# High_Freq.net
KiCad netlist of a schematic drawn in Altium Designer
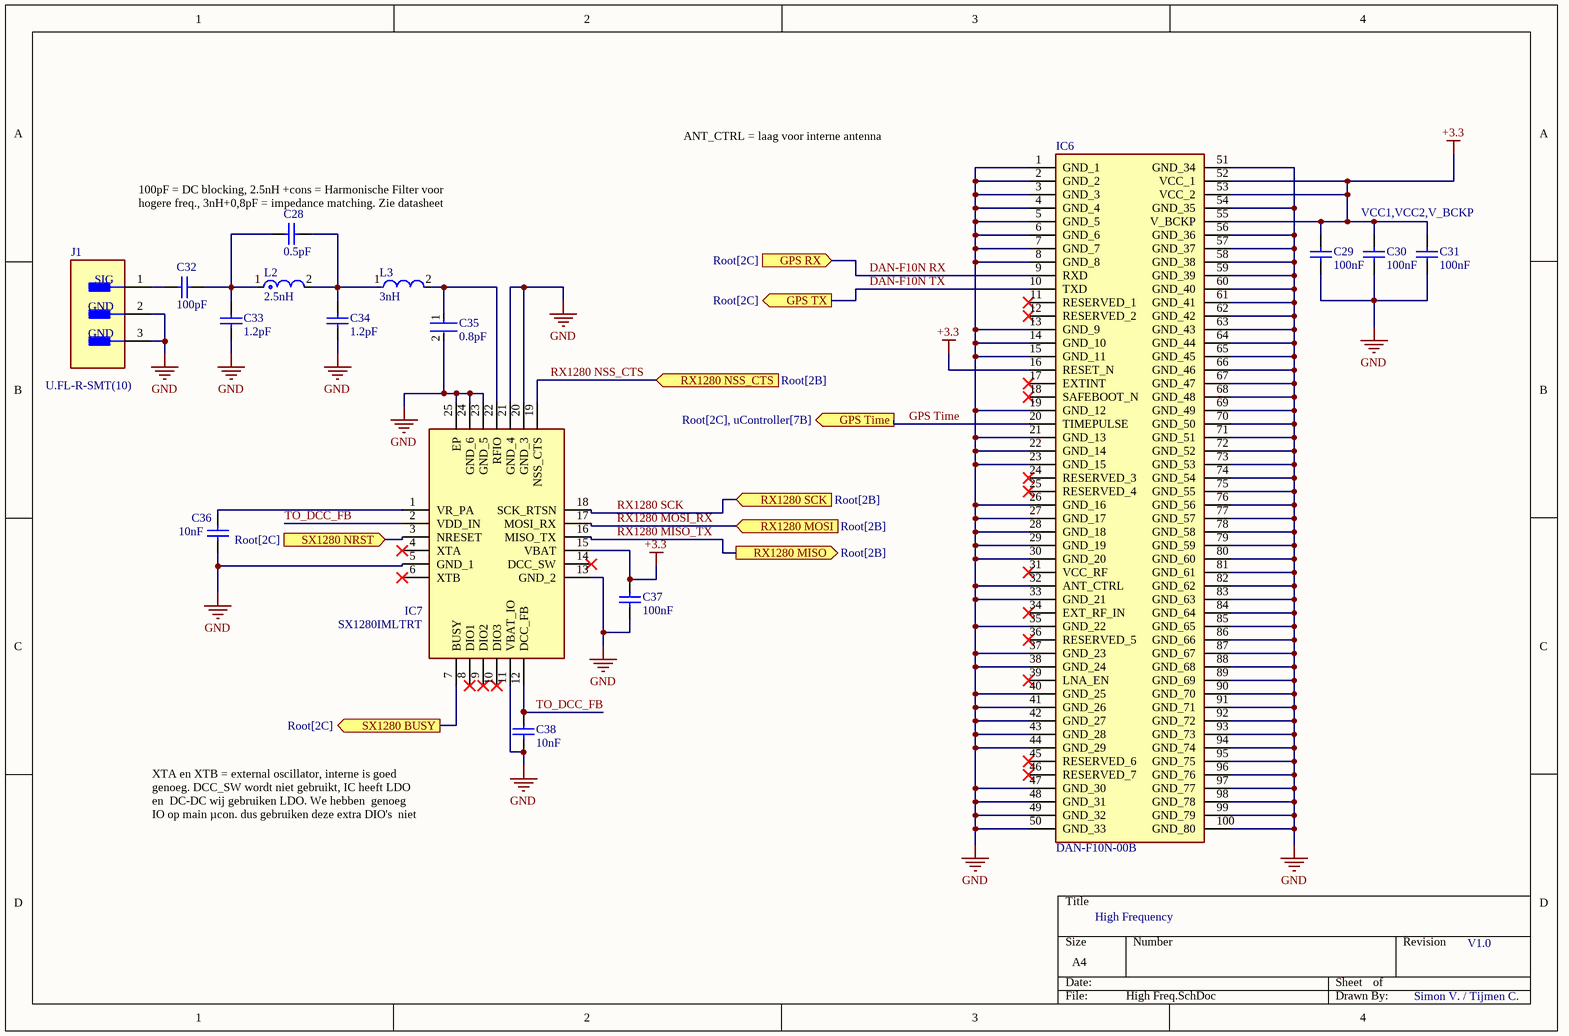
[diagram p0: High Freq.SchDoc]

(export (version "E")
  (design (tool "Eeschema 10.0.6"))
  (components
    (comp (ref "C28")
      (value "0.5pF")
      (footprint "CAPC0603(1608)100_M")
      (description "CAP 0.5pF 10V ±0.1pF 0603 (1608 Metric) Thickness 1mm SMD")
      (fields (field (name "TOLERANCE") "Â±0.1pF"))
      (libsource (lib "Altium Content Vault") (part "CAP"))
    )
    (comp (ref "C29")
      (value "100nF")
      (footprint "CAPC1608X92X38ML15T08")
      (fields (field (name "PART NUMBER") "VJ0603Y104MXXAC") (field (name "MANUFACTURER") "Vitramon"))
      (libsource (lib "Altium Content Vault") (part "CAP"))
    )
    (comp (ref "C30")
      (value "100nF")
      (footprint "CAPC1608X92X38ML15T08")
      (fields (field (name "PART NUMBER") "VJ0603Y104MXXAC") (field (name "MANUFACTURER") "Vitramon"))
      (libsource (lib "Altium Content Vault") (part "CAP"))
    )
    (comp (ref "C31")
      (value "100nF")
      (footprint "CAPC1608X92X38ML15T08")
      (fields (field (name "PART NUMBER") "VJ0603Y104MXXAC") (field (name "MANUFACTURER") "Vitramon"))
      (libsource (lib "Altium Content Vault") (part "CAP"))
    )
    (comp (ref "C32")
      (value "100pF")
      (footprint "CAPC1608X92X38NL15T08")
      (fields (field (name "MANUFACTURER") "Vitramon") (field (name "PART NUMBER") "VJ0603A101KXCAC"))
      (libsource (lib "Altium Content Vault") (part "CAP"))
    )
    (comp (ref "C33")
      (value "1.2pF")
      (footprint "CAPC1608X90X35NL15T15")
      (fields
        (field (name "MANUFACTURER") "AVX Interconnect / Elco")
        (field (name "PART NUMBER") "06031A1R2CAT2A")
      )
      (libsource (lib "Altium Content Vault") (part "CAP"))
    )
    (comp (ref "C34")
      (value "1.2pF")
      (footprint "CAPC1608X90X35NL15T15")
      (fields
        (field (name "MANUFACTURER") "AVX Interconnect / Elco")
        (field (name "PART NUMBER") "06031A1R2CAT2A")
      )
      (libsource (lib "Altium Content Vault") (part "CAP"))
    )
    (comp (ref "C35")
      (value "0.8pF")
      (footprint "FP-GCM188-0_1-IPC_C")
      (description "Ceramic Capacitor for Automotive 0.8pF  ±0.1pF 100VDC C0G 0603 Paper T/R")
      (libsource (lib "Altium Content Vault") (part "02cd4be3c70576c341d710602a673aa"))
    )
    (comp (ref "C36")
      (value "10nF")
      (footprint "CAPC1608X92X38LL15T08")
      (fields (field (name "MANUFACTURER") "Vitramon") (field (name "PART NUMBER") "VJ0603Y103JXXAC"))
      (libsource (lib "Altium Content Vault") (part "CAP"))
    )
    (comp (ref "C37")
      (value "100nF")
      (footprint "CAPC1608X92X38ML15T08")
      (fields (field (name "PART NUMBER") "VJ0603Y104MXXAC") (field (name "MANUFACTURER") "Vitramon"))
      (libsource (lib "Altium Content Vault") (part "CAP"))
    )
    (comp (ref "C38")
      (value "10nF")
      (footprint "CAPC1608X92X38LL15T08")
      (fields (field (name "MANUFACTURER") "Vitramon") (field (name "PART NUMBER") "VJ0603Y103JXXAC"))
      (libsource (lib "Altium Content Vault") (part "CAP"))
    )
    (comp (ref "IC6")
      (value "DAN-F10N-00B")
      (footprint "SamacSys:DANF10N00B")
      (description "Integrated Circuit")
      (libsource (lib "*") (part "DAN-F10N-00B"))
    )
    (comp (ref "IC7")
      (value "SX1280IMLTRT")
      (footprint "SamacSys:QFN50P400X400X100-25N-D")
      (description "Integrated Circuit")
      (fields (field (name "MOUSER PART NUMBER") "947-SX1280IMLTRT"))
      (libsource (lib "*") (part "SX1280IMLTRT"))
    )
    (comp (ref "J1")
      (value "U.FL-R-SMT(10)")
      (footprint "FP-U_FL-R-SMT_10-MFG")
      (description "CONN U.FL RCPT STR 50 OHM SMD")
      (libsource (lib "Altium Content Vault") (part "eef6fde44c591823e8076210edfe12f"))
    )
    (comp (ref "L2")
      (value "2.5nH")
      (footprint "FP-LQP03TG_02-IPC_A")
      (description "Film type RF Inductor 2.5nH ±0.1nH 500mA 0.2Ω 0201 (0603)")
      (libsource (lib "Altium Content Vault") (part "4cc4b267dca4c8e51f7102f422741d8"))
    )
    (comp (ref "L3")
      (value "3nH")
      (footprint "FP-LQW18AN_80-MFG")
      (description "Wire Wound RF Inductor 3nH ±0.2nH 670mA 0.17Ω 0603 (1608)")
      (libsource (lib "Altium Content Vault") (part "725321dda6339637d4d059423bc1c3c"))
    )
  )
  (nets
    (net (code "1") (name "+3.3") (class "Default")
      (node (ref "C29") (pin "2") (pinfunction "2_2") (pintype "passive"))
      (node (ref "C30") (pin "2") (pinfunction "2_2") (pintype "passive"))
      (node (ref "C31") (pin "2") (pinfunction "2_2") (pintype "passive"))
      (node (ref "C37") (pin "2") (pinfunction "2_2") (pintype "passive"))
      (node (ref "IC6") (pin "16") (pinfunction "RESET_N_16") (pintype "passive"))
      (node (ref "IC6") (pin "52") (pinfunction "VCC_1_52") (pintype "passive"))
      (node (ref "IC6") (pin "53") (pinfunction "VCC_2_53") (pintype "passive"))
      (node (ref "IC6") (pin "55") (pinfunction "V_BCKP_55") (pintype "passive"))
      (node (ref "IC7") (pin "15") (pinfunction "VBAT_15") (pintype "passive"))
    )
    (net (code "2") (name "/DAN-F10N RX") (class "Default")
      (node (ref "IC6") (pin "9") (pinfunction "RXD_9") (pintype "passive"))
    )
    (net (code "3") (name "/DAN-F10N TX") (class "Default")
      (node (ref "IC6") (pin "10") (pinfunction "TXD_10") (pintype "passive"))
    )
    (net (code "4") (name "/GPS Time") (class "Default")
      (node (ref "IC6") (pin "20") (pinfunction "TIMEPULSE_20") (pintype "passive"))
    )
    (net (code "5") (name "/RX1280 MISO_TX") (class "Default")
      (node (ref "IC7") (pin "16") (pinfunction "MISO_TX_16") (pintype "passive"))
    )
    (net (code "6") (name "/RX1280 MOSI_RX") (class "Default")
      (node (ref "IC7") (pin "17") (pinfunction "MOSI_RX_17") (pintype "passive"))
    )
    (net (code "7") (name "/RX1280 NSS_CTS") (class "Default")
      (node (ref "IC7") (pin "19") (pinfunction "NSS_CTS_19") (pintype "passive"))
    )
    (net (code "8") (name "/RX1280 SCK") (class "Default")
      (node (ref "IC7") (pin "18") (pinfunction "SCK_RTSN_18") (pintype "passive"))
    )
    (net (code "9") (name "/SX1280 BUSY") (class "Default")
      (node (ref "IC7") (pin "7") (pinfunction "BUSY_7") (pintype "passive"))
    )
    (net (code "10") (name "/SX1280 NRST") (class "Default")
      (node (ref "IC7") (pin "3") (pinfunction "NRESET_3") (pintype "passive"))
    )
    (net (code "11") (name "/TO_DCC_FB") (class "Default")
      (node (ref "C38") (pin "2") (pinfunction "2_2") (pintype "passive"))
      (node (ref "IC7") (pin "12") (pinfunction "DCC_FB_12") (pintype "passive"))
      (node (ref "IC7") (pin "2") (pinfunction "VDD_IN_2") (pintype "passive"))
    )
    (net (code "12") (name "GND") (class "Default")
      (node (ref "C29") (pin "1") (pinfunction "1_1") (pintype "passive"))
      (node (ref "C30") (pin "1") (pinfunction "1_1") (pintype "passive"))
      (node (ref "C31") (pin "1") (pinfunction "1_1") (pintype "passive"))
      (node (ref "C33") (pin "1") (pinfunction "1_1") (pintype "passive"))
      (node (ref "C34") (pin "1") (pinfunction "1_1") (pintype "passive"))
      (node (ref "C35") (pin "2") (pinfunction "2_2") (pintype "passive"))
      (node (ref "C36") (pin "1") (pinfunction "1_1") (pintype "passive"))
      (node (ref "C37") (pin "1") (pinfunction "1_1") (pintype "passive"))
      (node (ref "C38") (pin "1") (pinfunction "1_1") (pintype "passive"))
      (node (ref "IC6") (pin "1") (pinfunction "GND_1_1") (pintype "passive"))
      (node (ref "IC6") (pin "100") (pinfunction "GND_80_100") (pintype "passive"))
      (node (ref "IC6") (pin "13") (pinfunction "GND_9_13") (pintype "passive"))
      (node (ref "IC6") (pin "14") (pinfunction "GND_10_14") (pintype "passive"))
      (node (ref "IC6") (pin "15") (pinfunction "GND_11_15") (pintype "passive"))
      (node (ref "IC6") (pin "19") (pinfunction "GND_12_19") (pintype "passive"))
      (node (ref "IC6") (pin "2") (pinfunction "GND_2_2") (pintype "passive"))
      (node (ref "IC6") (pin "21") (pinfunction "GND_13_21") (pintype "passive"))
      (node (ref "IC6") (pin "22") (pinfunction "GND_14_22") (pintype "passive"))
      (node (ref "IC6") (pin "23") (pinfunction "GND_15_23") (pintype "passive"))
      (node (ref "IC6") (pin "26") (pinfunction "GND_16_26") (pintype "passive"))
      (node (ref "IC6") (pin "27") (pinfunction "GND_17_27") (pintype "passive"))
      (node (ref "IC6") (pin "28") (pinfunction "GND_18_28") (pintype "passive"))
      (node (ref "IC6") (pin "29") (pinfunction "GND_19_29") (pintype "passive"))
      (node (ref "IC6") (pin "3") (pinfunction "GND_3_3") (pintype "passive"))
      (node (ref "IC6") (pin "30") (pinfunction "GND_20_30") (pintype "passive"))
      (node (ref "IC6") (pin "32") (pinfunction "ANT_CTRL_32") (pintype "passive"))
      (node (ref "IC6") (pin "33") (pinfunction "GND_21_33") (pintype "passive"))
      (node (ref "IC6") (pin "35") (pinfunction "GND_22_35") (pintype "passive"))
      (node (ref "IC6") (pin "37") (pinfunction "GND_23_37") (pintype "passive"))
      (node (ref "IC6") (pin "38") (pinfunction "GND_24_38") (pintype "passive"))
      (node (ref "IC6") (pin "4") (pinfunction "GND_4_4") (pintype "passive"))
      (node (ref "IC6") (pin "40") (pinfunction "GND_25_40") (pintype "passive"))
      (node (ref "IC6") (pin "41") (pinfunction "GND_26_41") (pintype "passive"))
      (node (ref "IC6") (pin "42") (pinfunction "GND_27_42") (pintype "passive"))
      (node (ref "IC6") (pin "43") (pinfunction "GND_28_43") (pintype "passive"))
      (node (ref "IC6") (pin "44") (pinfunction "GND_29_44") (pintype "passive"))
      (node (ref "IC6") (pin "47") (pinfunction "GND_30_47") (pintype "passive"))
      (node (ref "IC6") (pin "48") (pinfunction "GND_31_48") (pintype "passive"))
      (node (ref "IC6") (pin "49") (pinfunction "GND_32_49") (pintype "passive"))
      (node (ref "IC6") (pin "5") (pinfunction "GND_5_5") (pintype "passive"))
      (node (ref "IC6") (pin "50") (pinfunction "GND_33_50") (pintype "passive"))
      (node (ref "IC6") (pin "51") (pinfunction "GND_34_51") (pintype "passive"))
      (node (ref "IC6") (pin "54") (pinfunction "GND_35_54") (pintype "passive"))
      (node (ref "IC6") (pin "56") (pinfunction "GND_36_56") (pintype "passive"))
      (node (ref "IC6") (pin "57") (pinfunction "GND_37_57") (pintype "passive"))
      (node (ref "IC6") (pin "58") (pinfunction "GND_38_58") (pintype "passive"))
      (node (ref "IC6") (pin "59") (pinfunction "GND_39_59") (pintype "passive"))
      (node (ref "IC6") (pin "6") (pinfunction "GND_6_6") (pintype "passive"))
      (node (ref "IC6") (pin "60") (pinfunction "GND_40_60") (pintype "passive"))
      (node (ref "IC6") (pin "61") (pinfunction "GND_41_61") (pintype "passive"))
      (node (ref "IC6") (pin "62") (pinfunction "GND_42_62") (pintype "passive"))
      (node (ref "IC6") (pin "63") (pinfunction "GND_43_63") (pintype "passive"))
      (node (ref "IC6") (pin "64") (pinfunction "GND_44_64") (pintype "passive"))
      (node (ref "IC6") (pin "65") (pinfunction "GND_45_65") (pintype "passive"))
      (node (ref "IC6") (pin "66") (pinfunction "GND_46_66") (pintype "passive"))
      (node (ref "IC6") (pin "67") (pinfunction "GND_47_67") (pintype "passive"))
      (node (ref "IC6") (pin "68") (pinfunction "GND_48_68") (pintype "passive"))
      (node (ref "IC6") (pin "69") (pinfunction "GND_49_69") (pintype "passive"))
      (node (ref "IC6") (pin "7") (pinfunction "GND_7_7") (pintype "passive"))
      (node (ref "IC6") (pin "70") (pinfunction "GND_50_70") (pintype "passive"))
      (node (ref "IC6") (pin "71") (pinfunction "GND_51_71") (pintype "passive"))
      (node (ref "IC6") (pin "72") (pinfunction "GND_52_72") (pintype "passive"))
      (node (ref "IC6") (pin "73") (pinfunction "GND_53_73") (pintype "passive"))
      (node (ref "IC6") (pin "74") (pinfunction "GND_54_74") (pintype "passive"))
      (node (ref "IC6") (pin "75") (pinfunction "GND_55_75") (pintype "passive"))
      (node (ref "IC6") (pin "76") (pinfunction "GND_56_76") (pintype "passive"))
      (node (ref "IC6") (pin "77") (pinfunction "GND_57_77") (pintype "passive"))
      (node (ref "IC6") (pin "78") (pinfunction "GND_58_78") (pintype "passive"))
      (node (ref "IC6") (pin "79") (pinfunction "GND_59_79") (pintype "passive"))
      (node (ref "IC6") (pin "8") (pinfunction "GND_8_8") (pintype "passive"))
      (node (ref "IC6") (pin "80") (pinfunction "GND_60_80") (pintype "passive"))
      (node (ref "IC6") (pin "81") (pinfunction "GND_61_81") (pintype "passive"))
      (node (ref "IC6") (pin "82") (pinfunction "GND_62_82") (pintype "passive"))
      (node (ref "IC6") (pin "83") (pinfunction "GND_63_83") (pintype "passive"))
      (node (ref "IC6") (pin "84") (pinfunction "GND_64_84") (pintype "passive"))
      (node (ref "IC6") (pin "85") (pinfunction "GND_65_85") (pintype "passive"))
      (node (ref "IC6") (pin "86") (pinfunction "GND_66_86") (pintype "passive"))
      (node (ref "IC6") (pin "87") (pinfunction "GND_67_87") (pintype "passive"))
      (node (ref "IC6") (pin "88") (pinfunction "GND_68_88") (pintype "passive"))
      (node (ref "IC6") (pin "89") (pinfunction "GND_69_89") (pintype "passive"))
      (node (ref "IC6") (pin "90") (pinfunction "GND_70_90") (pintype "passive"))
      (node (ref "IC6") (pin "91") (pinfunction "GND_71_91") (pintype "passive"))
      (node (ref "IC6") (pin "92") (pinfunction "GND_72_92") (pintype "passive"))
      (node (ref "IC6") (pin "93") (pinfunction "GND_73_93") (pintype "passive"))
      (node (ref "IC6") (pin "94") (pinfunction "GND_74_94") (pintype "passive"))
      (node (ref "IC6") (pin "95") (pinfunction "GND_75_95") (pintype "passive"))
      (node (ref "IC6") (pin "96") (pinfunction "GND_76_96") (pintype "passive"))
      (node (ref "IC6") (pin "97") (pinfunction "GND_77_97") (pintype "passive"))
      (node (ref "IC6") (pin "98") (pinfunction "GND_78_98") (pintype "passive"))
      (node (ref "IC6") (pin "99") (pinfunction "GND_79_99") (pintype "passive"))
      (node (ref "IC7") (pin "11") (pinfunction "VBAT_IO_11") (pintype "passive"))
      (node (ref "IC7") (pin "13") (pinfunction "GND_2_13") (pintype "passive"))
      (node (ref "IC7") (pin "20") (pinfunction "GND_3_20") (pintype "passive"))
      (node (ref "IC7") (pin "21") (pinfunction "GND_4_21") (pintype "passive"))
      (node (ref "IC7") (pin "23") (pinfunction "GND_5_23") (pintype "passive"))
      (node (ref "IC7") (pin "24") (pinfunction "GND_6_24") (pintype "passive"))
      (node (ref "IC7") (pin "25") (pinfunction "EP_25") (pintype "passive"))
      (node (ref "IC7") (pin "5") (pinfunction "GND_1_5") (pintype "passive"))
      (node (ref "J1") (pin "2") (pinfunction "GND_2") (pintype "power_in"))
      (node (ref "J1") (pin "3") (pinfunction "GND_3") (pintype "power_in"))
    )
    (net (code "13") (name "Net-(C28-Pad1)") (class "Default")
      (node (ref "C28") (pin "1") (pinfunction "1_1") (pintype "passive"))
      (node (ref "C32") (pin "2") (pinfunction "2_2") (pintype "passive"))
      (node (ref "C33") (pin "2") (pinfunction "2_2") (pintype "passive"))
      (node (ref "L2") (pin "1") (pinfunction "1_1") (pintype "passive"))
    )
    (net (code "14") (name "Net-(C28-Pad2)") (class "Default")
      (node (ref "C28") (pin "2") (pinfunction "2_2") (pintype "passive"))
      (node (ref "C34") (pin "2") (pinfunction "2_2") (pintype "passive"))
      (node (ref "L2") (pin "2") (pinfunction "2_2") (pintype "passive"))
      (node (ref "L3") (pin "1") (pinfunction "1_1") (pintype "passive"))
    )
    (net (code "15") (name "Net-(IC7-RFIO)") (class "Default")
      (node (ref "C35") (pin "1") (pinfunction "1_1") (pintype "passive"))
      (node (ref "IC7") (pin "22") (pinfunction "RFIO_22") (pintype "passive"))
      (node (ref "L3") (pin "2") (pinfunction "2_2") (pintype "passive"))
    )
    (net (code "16") (name "Net-(IC7-VR_PA)") (class "Default")
      (node (ref "C36") (pin "2") (pinfunction "2_2") (pintype "passive"))
      (node (ref "IC7") (pin "1") (pinfunction "VR_PA_1") (pintype "passive"))
    )
    (net (code "17") (name "Net-(J1-SIG)") (class "Default")
      (node (ref "C32") (pin "1") (pinfunction "1_1") (pintype "passive"))
      (node (ref "J1") (pin "1") (pinfunction "SIG_1") (pintype "passive"))
    )
    (net (code "18") (name "unconnected-(IC6-EXTINT-Pad17)") (class "Default")
      (node (ref "IC6") (pin "17") (pinfunction "EXTINT_17") (pintype "passive+no_connect"))
    )
    (net (code "19") (name "unconnected-(IC6-EXT_RF_IN-Pad34)") (class "Default")
      (node (ref "IC6") (pin "34") (pinfunction "EXT_RF_IN_34") (pintype "passive+no_connect"))
    )
    (net (code "20") (name "unconnected-(IC6-LNA_EN-Pad39)") (class "Default")
      (node (ref "IC6") (pin "39") (pinfunction "LNA_EN_39") (pintype "passive+no_connect"))
    )
    (net (code "21") (name "unconnected-(IC6-RESERVED_1-Pad11)") (class "Default")
      (node (ref "IC6") (pin "11") (pinfunction "RESERVED_1_11") (pintype "passive+no_connect"))
    )
    (net (code "22") (name "unconnected-(IC6-RESERVED_2-Pad12)") (class "Default")
      (node (ref "IC6") (pin "12") (pinfunction "RESERVED_2_12") (pintype "passive+no_connect"))
    )
    (net (code "23") (name "unconnected-(IC6-RESERVED_3-Pad24)") (class "Default")
      (node (ref "IC6") (pin "24") (pinfunction "RESERVED_3_24") (pintype "passive+no_connect"))
    )
    (net (code "24") (name "unconnected-(IC6-RESERVED_4-Pad25)") (class "Default")
      (node (ref "IC6") (pin "25") (pinfunction "RESERVED_4_25") (pintype "passive+no_connect"))
    )
    (net (code "25") (name "unconnected-(IC6-RESERVED_5-Pad36)") (class "Default")
      (node (ref "IC6") (pin "36") (pinfunction "RESERVED_5_36") (pintype "passive+no_connect"))
    )
    (net (code "26") (name "unconnected-(IC6-RESERVED_6-Pad45)") (class "Default")
      (node (ref "IC6") (pin "45") (pinfunction "RESERVED_6_45") (pintype "passive+no_connect"))
    )
    (net (code "27") (name "unconnected-(IC6-RESERVED_7-Pad46)") (class "Default")
      (node (ref "IC6") (pin "46") (pinfunction "RESERVED_7_46") (pintype "passive+no_connect"))
    )
    (net (code "28") (name "unconnected-(IC6-SAFEBOOT_N-Pad18)") (class "Default")
      (node (ref "IC6") (pin "18") (pinfunction "SAFEBOOT_N_18") (pintype "passive+no_connect"))
    )
    (net (code "29") (name "unconnected-(IC6-VCC_RF-Pad31)") (class "Default")
      (node (ref "IC6") (pin "31") (pinfunction "VCC_RF_31") (pintype "passive+no_connect"))
    )
    (net (code "30") (name "unconnected-(IC7-DCC_SW-Pad14)") (class "Default")
      (node (ref "IC7") (pin "14") (pinfunction "DCC_SW_14") (pintype "passive+no_connect"))
    )
    (net (code "31") (name "unconnected-(IC7-DIO1-Pad8)") (class "Default")
      (node (ref "IC7") (pin "8") (pinfunction "DIO1_8") (pintype "passive+no_connect"))
    )
    (net (code "32") (name "unconnected-(IC7-DIO2-Pad9)") (class "Default")
      (node (ref "IC7") (pin "9") (pinfunction "DIO2_9") (pintype "passive+no_connect"))
    )
    (net (code "33") (name "unconnected-(IC7-DIO3-Pad10)") (class "Default")
      (node (ref "IC7") (pin "10") (pinfunction "DIO3_10") (pintype "passive+no_connect"))
    )
    (net (code "34") (name "unconnected-(IC7-XTA-Pad4)") (class "Default")
      (node (ref "IC7") (pin "4") (pinfunction "XTA_4") (pintype "passive+no_connect"))
    )
    (net (code "35") (name "unconnected-(IC7-XTB-Pad6)") (class "Default")
      (node (ref "IC7") (pin "6") (pinfunction "XTB_6") (pintype "passive+no_connect"))
    )
  )
)
